# SensTPR.net
KiCad netlist of a schematic drawn in Altium Designer
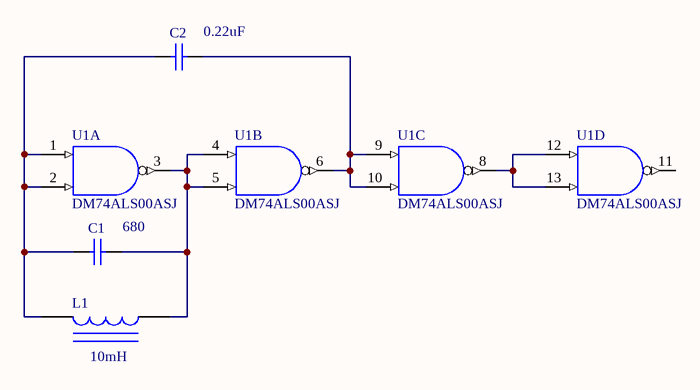
[diagram p0: SensTPR.SchDoc]

(export (version "E")
  (design (tool "Eeschema 10.0.6"))
  (components
    (comp (ref "C1")
      (value "680")
      (footprint "RAD-0.3")
      (description "Capacitor")
      (fields (field (name "Comment") "Cap") (field (name "PUBLISHER") "Altium Limited"))
      (libsource (lib "Miscellaneous Devices") (part "Cap"))
    )
    (comp (ref "C2")
      (value "0.22uF")
      (footprint "RAD-0.3")
      (description "Capacitor")
      (fields (field (name "Comment") "Cap") (field (name "PUBLISHER") "Altium Limited"))
      (libsource (lib "Miscellaneous Devices") (part "Cap"))
    )
    (comp (ref "L1")
      (value "10mH")
      (footprint "AXIAL-0.9")
      (description "Magnetic-Core Inductor")
      (fields (field (name "Comment") "Inductor Iron") (field (name "PUBLISHER") "Altium Limited"))
      (libsource (lib "Miscellaneous Devices") (part "Inductor Iron"))
    )
    (comp (ref "U1")
      (value "DM74ALS00ASJ")
      (footprint "M14D_N")
      (description "Quad 2-Input NAND Gate, 14-Pin SOP, Commerical Grade")
      (fields (field (name "PUBLISHER") "Altium Limited"))
      (libsource (lib "FSC Logic Gate") (part "DM74ALS00ASJ"))
    )
  )
  (nets
    (net (code "1") (name "GND") (class "Default")
      (node (ref "U1") (pin "7") (pinfunction "GND_7") (pintype "power_in"))
    )
    (net (code "2") (name "Net-(U1A-A)") (class "Default")
      (node (ref "C1") (pin "2") (pinfunction "2_2") (pintype "passive"))
      (node (ref "C2") (pin "2") (pinfunction "2_2") (pintype "passive"))
      (node (ref "L1") (pin "2") (pinfunction "2_2") (pintype "passive"))
      (node (ref "U1") (pin "1") (pinfunction "A_1") (pintype "input"))
      (node (ref "U1") (pin "2") (pinfunction "B_2") (pintype "input"))
    )
    (net (code "3") (name "Net-(U1A-Y)") (class "Default")
      (node (ref "C1") (pin "1") (pinfunction "1_1") (pintype "passive"))
      (node (ref "L1") (pin "1") (pinfunction "1_1") (pintype "passive"))
      (node (ref "U1") (pin "3") (pinfunction "Y_3") (pintype "output"))
      (node (ref "U1") (pin "4") (pinfunction "A_4") (pintype "input"))
      (node (ref "U1") (pin "5") (pinfunction "B_5") (pintype "input"))
    )
    (net (code "4") (name "Net-(U1B-Y)") (class "Default")
      (node (ref "C2") (pin "1") (pinfunction "1_1") (pintype "passive"))
      (node (ref "U1") (pin "10") (pinfunction "B_10") (pintype "input"))
      (node (ref "U1") (pin "6") (pinfunction "Y_6") (pintype "output"))
      (node (ref "U1") (pin "9") (pinfunction "A_9") (pintype "input"))
    )
    (net (code "5") (name "Net-(U1C-Y)") (class "Default")
      (node (ref "U1") (pin "12") (pinfunction "A_12") (pintype "input"))
      (node (ref "U1") (pin "13") (pinfunction "B_13") (pintype "input"))
      (node (ref "U1") (pin "8") (pinfunction "Y_8") (pintype "output"))
    )
    (net (code "6") (name "VCC") (class "Default")
      (node (ref "U1") (pin "14") (pinfunction "VCC_14") (pintype "power_in"))
    )
    (net (code "7") (name "unconnected-(U1D-Y-Pad11)") (class "Default")
      (node (ref "U1") (pin "11") (pinfunction "Y_11") (pintype "output"))
    )
  )
)
